# numpad.net
KiCad netlist of a schematic drawn in EAGLE
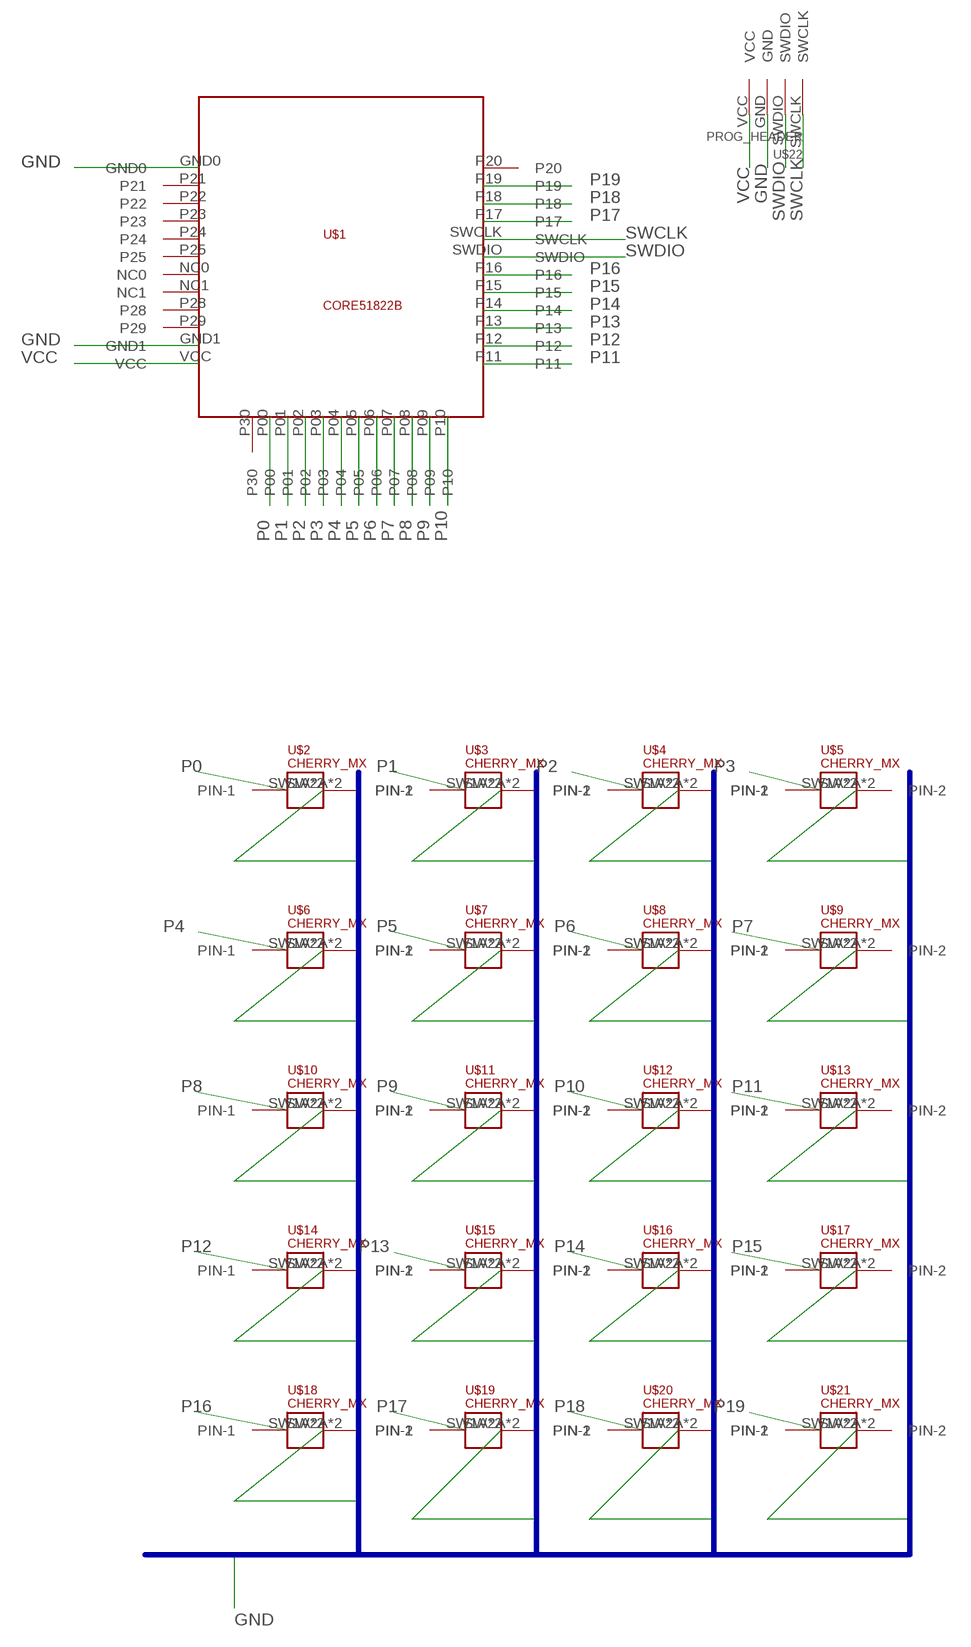
[diagram p0: schematic, sheet 1]

(export (version "E")
  (design (tool "Eeschema 10.0.6"))
  (components
    (comp (ref "U$1")
      (value "CORE51822B")
      (footprint "eagle-import:CORE51822B")
      (libsource (lib "eagle-import") (part "CORE51822B"))
    )
    (comp (ref "U$2")
      (value "CHERRY_MX")
      (footprint "eagle-import:CHERRY_MX")
      (libsource (lib "eagle-import") (part "CHERRY_MX"))
    )
    (comp (ref "U$3")
      (value "CHERRY_MX")
      (footprint "eagle-import:CHERRY_MX")
      (libsource (lib "eagle-import") (part "CHERRY_MX"))
    )
    (comp (ref "U$4")
      (value "CHERRY_MX")
      (footprint "eagle-import:CHERRY_MX")
      (libsource (lib "eagle-import") (part "CHERRY_MX"))
    )
    (comp (ref "U$5")
      (value "CHERRY_MX")
      (footprint "eagle-import:CHERRY_MX")
      (libsource (lib "eagle-import") (part "CHERRY_MX"))
    )
    (comp (ref "U$6")
      (value "CHERRY_MX")
      (footprint "eagle-import:CHERRY_MX")
      (libsource (lib "eagle-import") (part "CHERRY_MX"))
    )
    (comp (ref "U$7")
      (value "CHERRY_MX")
      (footprint "eagle-import:CHERRY_MX")
      (libsource (lib "eagle-import") (part "CHERRY_MX"))
    )
    (comp (ref "U$8")
      (value "CHERRY_MX")
      (footprint "eagle-import:CHERRY_MX")
      (libsource (lib "eagle-import") (part "CHERRY_MX"))
    )
    (comp (ref "U$9")
      (value "CHERRY_MX")
      (footprint "eagle-import:CHERRY_MX")
      (libsource (lib "eagle-import") (part "CHERRY_MX"))
    )
    (comp (ref "U$10")
      (value "CHERRY_MX")
      (footprint "eagle-import:CHERRY_MX")
      (libsource (lib "eagle-import") (part "CHERRY_MX"))
    )
    (comp (ref "U$11")
      (value "CHERRY_MX")
      (footprint "eagle-import:CHERRY_MX")
      (libsource (lib "eagle-import") (part "CHERRY_MX"))
    )
    (comp (ref "U$12")
      (value "CHERRY_MX")
      (footprint "eagle-import:CHERRY_MX")
      (libsource (lib "eagle-import") (part "CHERRY_MX"))
    )
    (comp (ref "U$13")
      (value "CHERRY_MX")
      (footprint "eagle-import:CHERRY_MX")
      (libsource (lib "eagle-import") (part "CHERRY_MX"))
    )
    (comp (ref "U$14")
      (value "CHERRY_MX")
      (footprint "eagle-import:CHERRY_MX")
      (libsource (lib "eagle-import") (part "CHERRY_MX"))
    )
    (comp (ref "U$15")
      (value "CHERRY_MX")
      (footprint "eagle-import:CHERRY_MX")
      (libsource (lib "eagle-import") (part "CHERRY_MX"))
    )
    (comp (ref "U$16")
      (value "CHERRY_MX")
      (footprint "eagle-import:CHERRY_MX")
      (libsource (lib "eagle-import") (part "CHERRY_MX"))
    )
    (comp (ref "U$17")
      (value "CHERRY_MX")
      (footprint "eagle-import:CHERRY_MX")
      (libsource (lib "eagle-import") (part "CHERRY_MX"))
    )
    (comp (ref "U$18")
      (value "CHERRY_MX")
      (footprint "eagle-import:CHERRY_MX")
      (libsource (lib "eagle-import") (part "CHERRY_MX"))
    )
    (comp (ref "U$19")
      (value "CHERRY_MX")
      (footprint "eagle-import:CHERRY_MX")
      (libsource (lib "eagle-import") (part "CHERRY_MX"))
    )
    (comp (ref "U$20")
      (value "CHERRY_MX")
      (footprint "eagle-import:CHERRY_MX")
      (libsource (lib "eagle-import") (part "CHERRY_MX"))
    )
    (comp (ref "U$21")
      (value "CHERRY_MX")
      (footprint "eagle-import:CHERRY_MX")
      (libsource (lib "eagle-import") (part "CHERRY_MX"))
    )
    (comp (ref "U$22")
      (value "PROG_HEADER")
      (footprint "eagle-import:PROG_HEADER")
      (libsource (lib "eagle-import") (part "PROG_HEADER"))
    )
  )
  (nets
    (net (code "1") (name "/B$1") (class "Default")
      (node (ref "U$10") (pin "SW2A") (pinfunction "PIN-2_SW2A") (pintype "bidirectional"))
      (node (ref "U$10") (pin "SW2B") (pinfunction "PIN-2_SW2B") (pintype "bidirectional"))
      (node (ref "U$11") (pin "SW2A") (pinfunction "PIN-2_SW2A") (pintype "bidirectional"))
      (node (ref "U$11") (pin "SW2B") (pinfunction "PIN-2_SW2B") (pintype "bidirectional"))
      (node (ref "U$12") (pin "SW2A") (pinfunction "PIN-2_SW2A") (pintype "bidirectional"))
      (node (ref "U$12") (pin "SW2B") (pinfunction "PIN-2_SW2B") (pintype "bidirectional"))
      (node (ref "U$13") (pin "SW2A") (pinfunction "PIN-2_SW2A") (pintype "bidirectional"))
      (node (ref "U$13") (pin "SW2B") (pinfunction "PIN-2_SW2B") (pintype "bidirectional"))
      (node (ref "U$14") (pin "SW2A") (pinfunction "PIN-2_SW2A") (pintype "bidirectional"))
      (node (ref "U$14") (pin "SW2B") (pinfunction "PIN-2_SW2B") (pintype "bidirectional"))
      (node (ref "U$15") (pin "SW2A") (pinfunction "PIN-2_SW2A") (pintype "bidirectional"))
      (node (ref "U$15") (pin "SW2B") (pinfunction "PIN-2_SW2B") (pintype "bidirectional"))
      (node (ref "U$16") (pin "SW2A") (pinfunction "PIN-2_SW2A") (pintype "bidirectional"))
      (node (ref "U$16") (pin "SW2B") (pinfunction "PIN-2_SW2B") (pintype "bidirectional"))
      (node (ref "U$17") (pin "SW2A") (pinfunction "PIN-2_SW2A") (pintype "bidirectional"))
      (node (ref "U$17") (pin "SW2B") (pinfunction "PIN-2_SW2B") (pintype "bidirectional"))
      (node (ref "U$18") (pin "SW2A") (pinfunction "PIN-2_SW2A") (pintype "bidirectional"))
      (node (ref "U$18") (pin "SW2B") (pinfunction "PIN-2_SW2B") (pintype "bidirectional"))
      (node (ref "U$19") (pin "SW2A") (pinfunction "PIN-2_SW2A") (pintype "bidirectional"))
      (node (ref "U$19") (pin "SW2B") (pinfunction "PIN-2_SW2B") (pintype "bidirectional"))
      (node (ref "U$2") (pin "SW2A") (pinfunction "PIN-2_SW2A") (pintype "bidirectional"))
      (node (ref "U$2") (pin "SW2B") (pinfunction "PIN-2_SW2B") (pintype "bidirectional"))
      (node (ref "U$20") (pin "SW2A") (pinfunction "PIN-2_SW2A") (pintype "bidirectional"))
      (node (ref "U$20") (pin "SW2B") (pinfunction "PIN-2_SW2B") (pintype "bidirectional"))
      (node (ref "U$21") (pin "SW2A") (pinfunction "PIN-2_SW2A") (pintype "bidirectional"))
      (node (ref "U$21") (pin "SW2B") (pinfunction "PIN-2_SW2B") (pintype "bidirectional"))
      (node (ref "U$3") (pin "SW2A") (pinfunction "PIN-2_SW2A") (pintype "bidirectional"))
      (node (ref "U$3") (pin "SW2B") (pinfunction "PIN-2_SW2B") (pintype "bidirectional"))
      (node (ref "U$4") (pin "SW2A") (pinfunction "PIN-2_SW2A") (pintype "bidirectional"))
      (node (ref "U$4") (pin "SW2B") (pinfunction "PIN-2_SW2B") (pintype "bidirectional"))
      (node (ref "U$5") (pin "SW2A") (pinfunction "PIN-2_SW2A") (pintype "bidirectional"))
      (node (ref "U$5") (pin "SW2B") (pinfunction "PIN-2_SW2B") (pintype "bidirectional"))
      (node (ref "U$6") (pin "SW2A") (pinfunction "PIN-2_SW2A") (pintype "bidirectional"))
      (node (ref "U$6") (pin "SW2B") (pinfunction "PIN-2_SW2B") (pintype "bidirectional"))
      (node (ref "U$7") (pin "SW2A") (pinfunction "PIN-2_SW2A") (pintype "bidirectional"))
      (node (ref "U$7") (pin "SW2B") (pinfunction "PIN-2_SW2B") (pintype "bidirectional"))
      (node (ref "U$8") (pin "SW2A") (pinfunction "PIN-2_SW2A") (pintype "bidirectional"))
      (node (ref "U$8") (pin "SW2B") (pinfunction "PIN-2_SW2B") (pintype "bidirectional"))
      (node (ref "U$9") (pin "SW2A") (pinfunction "PIN-2_SW2A") (pintype "bidirectional"))
      (node (ref "U$9") (pin "SW2B") (pinfunction "PIN-2_SW2B") (pintype "bidirectional"))
    )
    (net (code "2") (name "/GND") (class "Default")
      (node (ref "U$1") (pin "GND0") (pinfunction "GND0_GND0") (pintype "bidirectional"))
      (node (ref "U$1") (pin "GND1") (pinfunction "GND1_GND1") (pintype "bidirectional"))
      (node (ref "U$22") (pin "GND") (pinfunction "GND_GND") (pintype "bidirectional"))
    )
    (net (code "3") (name "/P0") (class "Default")
      (node (ref "U$1") (pin "P00") (pinfunction "P00_P00") (pintype "bidirectional"))
      (node (ref "U$2") (pin "SW1A") (pinfunction "PIN-1_SW1A") (pintype "bidirectional"))
      (node (ref "U$2") (pin "SW1B") (pinfunction "PIN-1_SW1B") (pintype "bidirectional"))
    )
    (net (code "4") (name "/P1") (class "Default")
      (node (ref "U$1") (pin "P01") (pinfunction "P01_P01") (pintype "bidirectional"))
      (node (ref "U$3") (pin "SW1A") (pinfunction "PIN-1_SW1A") (pintype "bidirectional"))
      (node (ref "U$3") (pin "SW1B") (pinfunction "PIN-1_SW1B") (pintype "bidirectional"))
    )
    (net (code "5") (name "/P2") (class "Default")
      (node (ref "U$1") (pin "P02") (pinfunction "P02_P02") (pintype "bidirectional"))
      (node (ref "U$4") (pin "SW1A") (pinfunction "PIN-1_SW1A") (pintype "bidirectional"))
      (node (ref "U$4") (pin "SW1B") (pinfunction "PIN-1_SW1B") (pintype "bidirectional"))
    )
    (net (code "6") (name "/P3") (class "Default")
      (node (ref "U$1") (pin "P03") (pinfunction "P03_P03") (pintype "bidirectional"))
      (node (ref "U$5") (pin "SW1A") (pinfunction "PIN-1_SW1A") (pintype "bidirectional"))
      (node (ref "U$5") (pin "SW1B") (pinfunction "PIN-1_SW1B") (pintype "bidirectional"))
    )
    (net (code "7") (name "/P4") (class "Default")
      (node (ref "U$1") (pin "P04") (pinfunction "P04_P04") (pintype "bidirectional"))
      (node (ref "U$6") (pin "SW1A") (pinfunction "PIN-1_SW1A") (pintype "bidirectional"))
      (node (ref "U$6") (pin "SW1B") (pinfunction "PIN-1_SW1B") (pintype "bidirectional"))
    )
    (net (code "8") (name "/P5") (class "Default")
      (node (ref "U$1") (pin "P05") (pinfunction "P05_P05") (pintype "bidirectional"))
      (node (ref "U$7") (pin "SW1A") (pinfunction "PIN-1_SW1A") (pintype "bidirectional"))
      (node (ref "U$7") (pin "SW1B") (pinfunction "PIN-1_SW1B") (pintype "bidirectional"))
    )
    (net (code "9") (name "/P6") (class "Default")
      (node (ref "U$1") (pin "P06") (pinfunction "P06_P06") (pintype "bidirectional"))
      (node (ref "U$8") (pin "SW1A") (pinfunction "PIN-1_SW1A") (pintype "bidirectional"))
      (node (ref "U$8") (pin "SW1B") (pinfunction "PIN-1_SW1B") (pintype "bidirectional"))
    )
    (net (code "10") (name "/P7") (class "Default")
      (node (ref "U$1") (pin "P07") (pinfunction "P07_P07") (pintype "bidirectional"))
      (node (ref "U$9") (pin "SW1A") (pinfunction "PIN-1_SW1A") (pintype "bidirectional"))
      (node (ref "U$9") (pin "SW1B") (pinfunction "PIN-1_SW1B") (pintype "bidirectional"))
    )
    (net (code "11") (name "/P8") (class "Default")
      (node (ref "U$1") (pin "P08") (pinfunction "P08_P08") (pintype "bidirectional"))
      (node (ref "U$10") (pin "SW1A") (pinfunction "PIN-1_SW1A") (pintype "bidirectional"))
      (node (ref "U$10") (pin "SW1B") (pinfunction "PIN-1_SW1B") (pintype "bidirectional"))
    )
    (net (code "12") (name "/P9") (class "Default")
      (node (ref "U$1") (pin "P09") (pinfunction "P09_P09") (pintype "bidirectional"))
      (node (ref "U$11") (pin "SW1A") (pinfunction "PIN-1_SW1A") (pintype "bidirectional"))
      (node (ref "U$11") (pin "SW1B") (pinfunction "PIN-1_SW1B") (pintype "bidirectional"))
    )
    (net (code "13") (name "/P10") (class "Default")
      (node (ref "U$1") (pin "P10") (pinfunction "P10_P10") (pintype "bidirectional"))
      (node (ref "U$12") (pin "SW1A") (pinfunction "PIN-1_SW1A") (pintype "bidirectional"))
      (node (ref "U$12") (pin "SW1B") (pinfunction "PIN-1_SW1B") (pintype "bidirectional"))
    )
    (net (code "14") (name "/P11") (class "Default")
      (node (ref "U$1") (pin "P11") (pinfunction "P11_P11") (pintype "bidirectional"))
      (node (ref "U$13") (pin "SW1A") (pinfunction "PIN-1_SW1A") (pintype "bidirectional"))
      (node (ref "U$13") (pin "SW1B") (pinfunction "PIN-1_SW1B") (pintype "bidirectional"))
    )
    (net (code "15") (name "/P12") (class "Default")
      (node (ref "U$1") (pin "P12") (pinfunction "P12_P12") (pintype "bidirectional"))
      (node (ref "U$14") (pin "SW1A") (pinfunction "PIN-1_SW1A") (pintype "bidirectional"))
      (node (ref "U$14") (pin "SW1B") (pinfunction "PIN-1_SW1B") (pintype "bidirectional"))
    )
    (net (code "16") (name "/P13") (class "Default")
      (node (ref "U$1") (pin "P13") (pinfunction "P13_P13") (pintype "bidirectional"))
      (node (ref "U$15") (pin "SW1A") (pinfunction "PIN-1_SW1A") (pintype "bidirectional"))
      (node (ref "U$15") (pin "SW1B") (pinfunction "PIN-1_SW1B") (pintype "bidirectional"))
    )
    (net (code "17") (name "/P14") (class "Default")
      (node (ref "U$1") (pin "P14") (pinfunction "P14_P14") (pintype "bidirectional"))
      (node (ref "U$16") (pin "SW1A") (pinfunction "PIN-1_SW1A") (pintype "bidirectional"))
      (node (ref "U$16") (pin "SW1B") (pinfunction "PIN-1_SW1B") (pintype "bidirectional"))
    )
    (net (code "18") (name "/P15") (class "Default")
      (node (ref "U$1") (pin "P15") (pinfunction "P15_P15") (pintype "bidirectional"))
      (node (ref "U$17") (pin "SW1A") (pinfunction "PIN-1_SW1A") (pintype "bidirectional"))
      (node (ref "U$17") (pin "SW1B") (pinfunction "PIN-1_SW1B") (pintype "bidirectional"))
    )
    (net (code "19") (name "/P16") (class "Default")
      (node (ref "U$1") (pin "P16") (pinfunction "P16_P16") (pintype "bidirectional"))
      (node (ref "U$18") (pin "SW1A") (pinfunction "PIN-1_SW1A") (pintype "bidirectional"))
      (node (ref "U$18") (pin "SW1B") (pinfunction "PIN-1_SW1B") (pintype "bidirectional"))
    )
    (net (code "20") (name "/P17") (class "Default")
      (node (ref "U$1") (pin "P17") (pinfunction "P17_P17") (pintype "bidirectional"))
      (node (ref "U$19") (pin "SW1A") (pinfunction "PIN-1_SW1A") (pintype "bidirectional"))
      (node (ref "U$19") (pin "SW1B") (pinfunction "PIN-1_SW1B") (pintype "bidirectional"))
    )
    (net (code "21") (name "/P18") (class "Default")
      (node (ref "U$1") (pin "P18") (pinfunction "P18_P18") (pintype "bidirectional"))
      (node (ref "U$20") (pin "SW1A") (pinfunction "PIN-1_SW1A") (pintype "bidirectional"))
      (node (ref "U$20") (pin "SW1B") (pinfunction "PIN-1_SW1B") (pintype "bidirectional"))
    )
    (net (code "22") (name "/P19") (class "Default")
      (node (ref "U$1") (pin "P19") (pinfunction "P19_P19") (pintype "bidirectional"))
      (node (ref "U$21") (pin "SW1A") (pinfunction "PIN-1_SW1A") (pintype "bidirectional"))
      (node (ref "U$21") (pin "SW1B") (pinfunction "PIN-1_SW1B") (pintype "bidirectional"))
    )
    (net (code "23") (name "/SWCLK") (class "Default")
      (node (ref "U$1") (pin "SWCLK") (pinfunction "SWCLK_SWCLK") (pintype "bidirectional"))
      (node (ref "U$22") (pin "SWCLK") (pinfunction "SWCLK_SWCLK") (pintype "bidirectional"))
    )
    (net (code "24") (name "/SWDIO") (class "Default")
      (node (ref "U$1") (pin "SWDIO") (pinfunction "SWDIO_SWDIO") (pintype "bidirectional"))
      (node (ref "U$22") (pin "SWDIO") (pinfunction "SWDIO_SWDIO") (pintype "bidirectional"))
    )
    (net (code "25") (name "/VCC") (class "Default")
      (node (ref "U$1") (pin "VCC") (pinfunction "VCC_VCC") (pintype "bidirectional"))
      (node (ref "U$22") (pin "VCC") (pinfunction "VCC_VCC") (pintype "bidirectional"))
    )
    (net (code "26") (name "unconnected-(U$1-PadNC0)") (class "Default")
      (node (ref "U$1") (pin "NC0") (pinfunction "NC0_NC0") (pintype "bidirectional"))
    )
    (net (code "27") (name "unconnected-(U$1-PadNC1)") (class "Default")
      (node (ref "U$1") (pin "NC1") (pinfunction "NC1_NC1") (pintype "bidirectional"))
    )
    (net (code "28") (name "unconnected-(U$1-PadP20)") (class "Default")
      (node (ref "U$1") (pin "P20") (pinfunction "P20_P20") (pintype "bidirectional"))
    )
    (net (code "29") (name "unconnected-(U$1-PadP21)") (class "Default")
      (node (ref "U$1") (pin "P21") (pinfunction "P21_P21") (pintype "bidirectional"))
    )
    (net (code "30") (name "unconnected-(U$1-PadP22)") (class "Default")
      (node (ref "U$1") (pin "P22") (pinfunction "P22_P22") (pintype "bidirectional"))
    )
    (net (code "31") (name "unconnected-(U$1-PadP23)") (class "Default")
      (node (ref "U$1") (pin "P23") (pinfunction "P23_P23") (pintype "bidirectional"))
    )
    (net (code "32") (name "unconnected-(U$1-PadP24)") (class "Default")
      (node (ref "U$1") (pin "P24") (pinfunction "P24_P24") (pintype "bidirectional"))
    )
    (net (code "33") (name "unconnected-(U$1-PadP25)") (class "Default")
      (node (ref "U$1") (pin "P25") (pinfunction "P25_P25") (pintype "bidirectional"))
    )
    (net (code "34") (name "unconnected-(U$1-PadP28)") (class "Default")
      (node (ref "U$1") (pin "P28") (pinfunction "P28_P28") (pintype "bidirectional"))
    )
    (net (code "35") (name "unconnected-(U$1-PadP29)") (class "Default")
      (node (ref "U$1") (pin "P29") (pinfunction "P29_P29") (pintype "bidirectional"))
    )
    (net (code "36") (name "unconnected-(U$1-PadP30)") (class "Default")
      (node (ref "U$1") (pin "P30") (pinfunction "P30_P30") (pintype "bidirectional"))
    )
  )
)
